# working.net
KiCad netlist of a schematic drawn in EAGLE
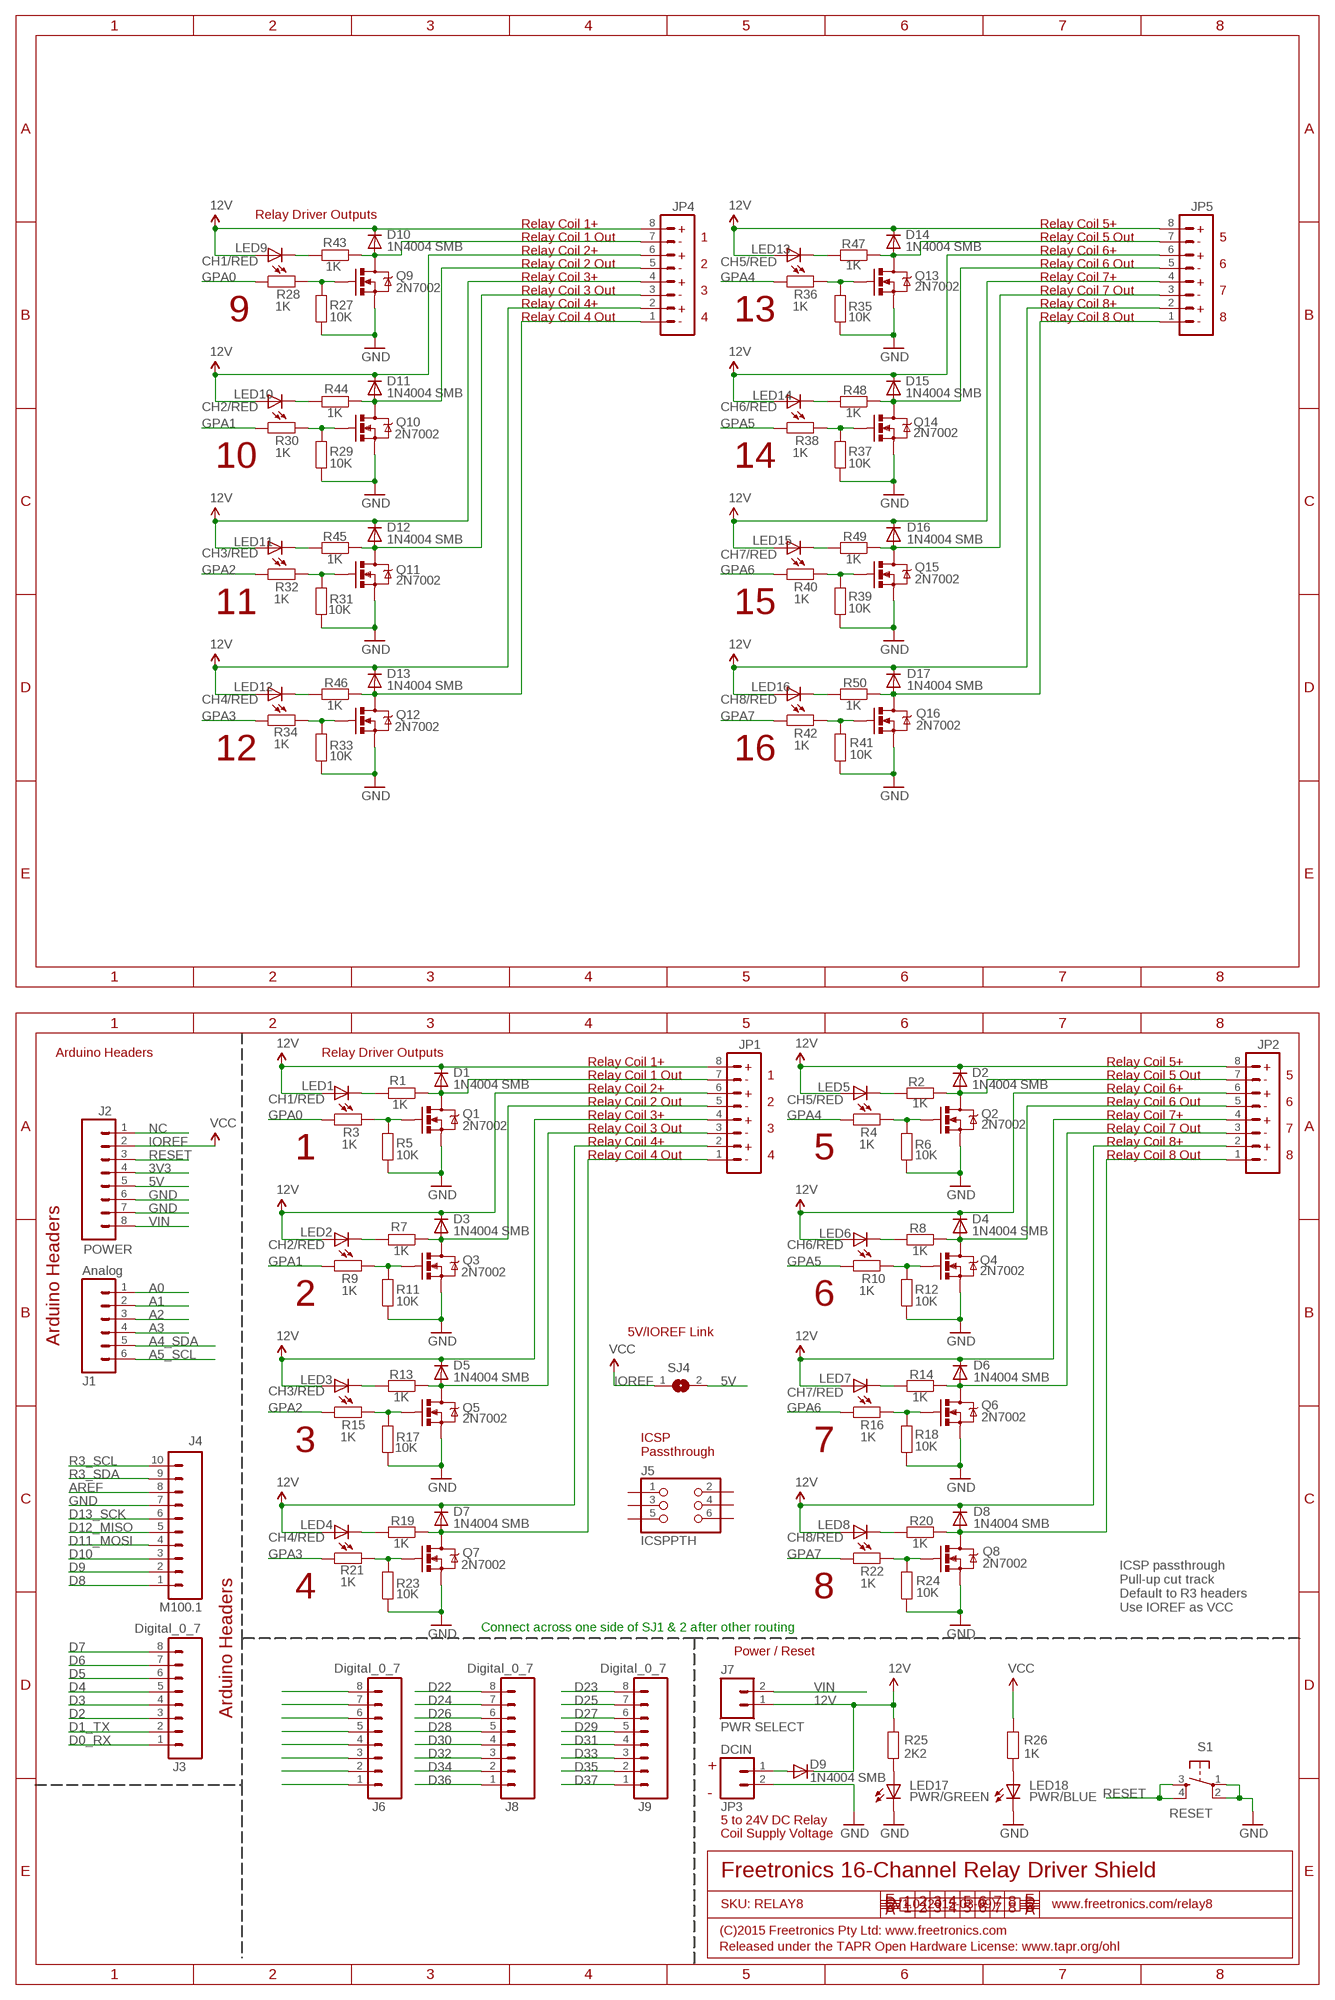
[diagram p0: schematic, sheet 1]

(export (version "E")
  (design (tool "Eeschema 10.0.6"))
  (components
    (comp (ref "D1")
      (value "1N4004 SMB")
      (footprint "eagle-import:SMB-DIODE")
      (libsource (lib "eagle-import") (part "DIODESMB"))
    )
    (comp (ref "D2")
      (value "1N4004 SMB")
      (footprint "eagle-import:SMB-DIODE")
      (libsource (lib "eagle-import") (part "DIODESMB"))
    )
    (comp (ref "D3")
      (value "1N4004 SMB")
      (footprint "eagle-import:SMB-DIODE")
      (libsource (lib "eagle-import") (part "DIODESMB"))
    )
    (comp (ref "D4")
      (value "1N4004 SMB")
      (footprint "eagle-import:SMB-DIODE")
      (libsource (lib "eagle-import") (part "DIODESMB"))
    )
    (comp (ref "D5")
      (value "1N4004 SMB")
      (footprint "eagle-import:SMB-DIODE")
      (libsource (lib "eagle-import") (part "DIODESMB"))
    )
    (comp (ref "D6")
      (value "1N4004 SMB")
      (footprint "eagle-import:SMB-DIODE")
      (libsource (lib "eagle-import") (part "DIODESMB"))
    )
    (comp (ref "D7")
      (value "1N4004 SMB")
      (footprint "eagle-import:SMB-DIODE")
      (libsource (lib "eagle-import") (part "DIODESMB"))
    )
    (comp (ref "D8")
      (value "1N4004 SMB")
      (footprint "eagle-import:SMB-DIODE")
      (libsource (lib "eagle-import") (part "DIODESMB"))
    )
    (comp (ref "D9")
      (value "1N4004 SMB")
      (footprint "eagle-import:SMB-DIODE")
      (libsource (lib "eagle-import") (part "DIODESMB"))
    )
    (comp (ref "D10")
      (value "1N4004 SMB")
      (footprint "eagle-import:SMB-DIODE")
      (libsource (lib "eagle-import") (part "DIODESMB"))
    )
    (comp (ref "D11")
      (value "1N4004 SMB")
      (footprint "eagle-import:SMB-DIODE")
      (libsource (lib "eagle-import") (part "DIODESMB"))
    )
    (comp (ref "D12")
      (value "1N4004 SMB")
      (footprint "eagle-import:SMB-DIODE")
      (libsource (lib "eagle-import") (part "DIODESMB"))
    )
    (comp (ref "D13")
      (value "1N4004 SMB")
      (footprint "eagle-import:SMB-DIODE")
      (libsource (lib "eagle-import") (part "DIODESMB"))
    )
    (comp (ref "D14")
      (value "1N4004 SMB")
      (footprint "eagle-import:SMB-DIODE")
      (libsource (lib "eagle-import") (part "DIODESMB"))
    )
    (comp (ref "D15")
      (value "1N4004 SMB")
      (footprint "eagle-import:SMB-DIODE")
      (libsource (lib "eagle-import") (part "DIODESMB"))
    )
    (comp (ref "D16")
      (value "1N4004 SMB")
      (footprint "eagle-import:SMB-DIODE")
      (libsource (lib "eagle-import") (part "DIODESMB"))
    )
    (comp (ref "D17")
      (value "1N4004 SMB")
      (footprint "eagle-import:SMB-DIODE")
      (libsource (lib "eagle-import") (part "DIODESMB"))
    )
    (comp (ref "J1")
      (value "Analog")
      (footprint "eagle-import:1X06")
      (libsource (lib "eagle-import") (part "M06SIP"))
    )
    (comp (ref "J2")
      (value "POWER")
      (footprint "eagle-import:1X08")
      (libsource (lib "eagle-import") (part "M08"))
    )
    (comp (ref "J3")
      (value "Digital_0_7")
      (footprint "eagle-import:1X08")
      (libsource (lib "eagle-import") (part "M08"))
    )
    (comp (ref "J4")
      (value "M100.1")
      (footprint "eagle-import:1X10")
      (libsource (lib "eagle-import") (part "M100.1"))
    )
    (comp (ref "J5")
      (value "ICSPPTH")
      (footprint "eagle-import:2X03PTH")
      (libsource (lib "eagle-import") (part "ICSPPTH"))
    )
    (comp (ref "J6")
      (value "Digital_0_7")
      (footprint "eagle-import:1X08")
      (libsource (lib "eagle-import") (part "M08"))
    )
    (comp (ref "J7")
      (value "PWR SELECT")
      (footprint "eagle-import:1X02")
      (libsource (lib "eagle-import") (part "M02PTH"))
    )
    (comp (ref "J8")
      (value "Digital_0_7")
      (footprint "eagle-import:1X08")
      (libsource (lib "eagle-import") (part "M08"))
    )
    (comp (ref "J9")
      (value "Digital_0_7")
      (footprint "eagle-import:1X08")
      (libsource (lib "eagle-import") (part "M08"))
    )
    (comp (ref "JP1")
      (value "M08")
      (footprint "eagle-import:TERMINALBLOCK_3.5MM_8")
      (libsource (lib "eagle-import") (part "freetronics-master-v1_M08"))
    )
    (comp (ref "JP2")
      (value "M08")
      (footprint "eagle-import:TERMINALBLOCK_3.5MM_8")
      (libsource (lib "eagle-import") (part "freetronics-master-v1_M08"))
    )
    (comp (ref "JP3")
      (value "DCIN")
      (footprint "eagle-import:SCREWTERMINAL-3.5MM-2")
      (libsource (lib "eagle-import") (part "freetronics-master-v1.1_M023.5MM"))
    )
    (comp (ref "JP4")
      (value "M08")
      (footprint "eagle-import:TERMINALBLOCK_3.5MM_8")
      (libsource (lib "eagle-import") (part "freetronics-master-v1_M08"))
    )
    (comp (ref "JP5")
      (value "M08")
      (footprint "eagle-import:TERMINALBLOCK_3.5MM_8")
      (libsource (lib "eagle-import") (part "freetronics-master-v1_M08"))
    )
    (comp (ref "LED1")
      (value "CH1/RED")
      (footprint "eagle-import:LED-0603")
      (libsource (lib "eagle-import") (part "LED0603"))
    )
    (comp (ref "LED2")
      (value "CH2/RED")
      (footprint "eagle-import:LED-0603")
      (libsource (lib "eagle-import") (part "LED0603"))
    )
    (comp (ref "LED3")
      (value "CH3/RED")
      (footprint "eagle-import:LED-0603")
      (libsource (lib "eagle-import") (part "LED0603"))
    )
    (comp (ref "LED4")
      (value "CH4/RED")
      (footprint "eagle-import:LED-0603")
      (libsource (lib "eagle-import") (part "LED0603"))
    )
    (comp (ref "LED5")
      (value "CH5/RED")
      (footprint "eagle-import:LED-0603")
      (libsource (lib "eagle-import") (part "LED0603"))
    )
    (comp (ref "LED6")
      (value "CH6/RED")
      (footprint "eagle-import:LED-0603")
      (libsource (lib "eagle-import") (part "LED0603"))
    )
    (comp (ref "LED7")
      (value "CH7/RED")
      (footprint "eagle-import:LED-0603")
      (libsource (lib "eagle-import") (part "LED0603"))
    )
    (comp (ref "LED8")
      (value "CH8/RED")
      (footprint "eagle-import:LED-0603")
      (libsource (lib "eagle-import") (part "LED0603"))
    )
    (comp (ref "LED9")
      (value "CH1/RED")
      (footprint "eagle-import:LED-0603")
      (libsource (lib "eagle-import") (part "LED0603"))
    )
    (comp (ref "LED10")
      (value "CH2/RED")
      (footprint "eagle-import:LED-0603")
      (libsource (lib "eagle-import") (part "LED0603"))
    )
    (comp (ref "LED11")
      (value "CH3/RED")
      (footprint "eagle-import:LED-0603")
      (libsource (lib "eagle-import") (part "LED0603"))
    )
    (comp (ref "LED12")
      (value "CH4/RED")
      (footprint "eagle-import:LED-0603")
      (libsource (lib "eagle-import") (part "LED0603"))
    )
    (comp (ref "LED13")
      (value "CH5/RED")
      (footprint "eagle-import:LED-0603")
      (libsource (lib "eagle-import") (part "LED0603"))
    )
    (comp (ref "LED14")
      (value "CH6/RED")
      (footprint "eagle-import:LED-0603")
      (libsource (lib "eagle-import") (part "LED0603"))
    )
    (comp (ref "LED15")
      (value "CH7/RED")
      (footprint "eagle-import:LED-0603")
      (libsource (lib "eagle-import") (part "LED0603"))
    )
    (comp (ref "LED16")
      (value "CH8/RED")
      (footprint "eagle-import:LED-0603")
      (libsource (lib "eagle-import") (part "LED0603"))
    )
    (comp (ref "LED17")
      (value "PWR/GREEN")
      (footprint "eagle-import:LED-0603")
      (libsource (lib "eagle-import") (part "LED0603"))
    )
    (comp (ref "LED18")
      (value "PWR/BLUE")
      (footprint "eagle-import:LED-0603")
      (libsource (lib "eagle-import") (part "LED0603"))
    )
    (comp (ref "Q1")
      (value "2N7002")
      (footprint "eagle-import:SOT23-3")
      (libsource (lib "eagle-import") (part "MOSFET-NCHANNELSMD"))
    )
    (comp (ref "Q2")
      (value "2N7002")
      (footprint "eagle-import:SOT23-3")
      (libsource (lib "eagle-import") (part "MOSFET-NCHANNELSMD"))
    )
    (comp (ref "Q3")
      (value "2N7002")
      (footprint "eagle-import:SOT23-3")
      (libsource (lib "eagle-import") (part "MOSFET-NCHANNELSMD"))
    )
    (comp (ref "Q4")
      (value "2N7002")
      (footprint "eagle-import:SOT23-3")
      (libsource (lib "eagle-import") (part "MOSFET-NCHANNELSMD"))
    )
    (comp (ref "Q5")
      (value "2N7002")
      (footprint "eagle-import:SOT23-3")
      (libsource (lib "eagle-import") (part "MOSFET-NCHANNELSMD"))
    )
    (comp (ref "Q6")
      (value "2N7002")
      (footprint "eagle-import:SOT23-3")
      (libsource (lib "eagle-import") (part "MOSFET-NCHANNELSMD"))
    )
    (comp (ref "Q7")
      (value "2N7002")
      (footprint "eagle-import:SOT23-3")
      (libsource (lib "eagle-import") (part "MOSFET-NCHANNELSMD"))
    )
    (comp (ref "Q8")
      (value "2N7002")
      (footprint "eagle-import:SOT23-3")
      (libsource (lib "eagle-import") (part "MOSFET-NCHANNELSMD"))
    )
    (comp (ref "Q9")
      (value "2N7002")
      (footprint "eagle-import:SOT23-3")
      (libsource (lib "eagle-import") (part "MOSFET-NCHANNELSMD"))
    )
    (comp (ref "Q10")
      (value "2N7002")
      (footprint "eagle-import:SOT23-3")
      (libsource (lib "eagle-import") (part "MOSFET-NCHANNELSMD"))
    )
    (comp (ref "Q11")
      (value "2N7002")
      (footprint "eagle-import:SOT23-3")
      (libsource (lib "eagle-import") (part "MOSFET-NCHANNELSMD"))
    )
    (comp (ref "Q12")
      (value "2N7002")
      (footprint "eagle-import:SOT23-3")
      (libsource (lib "eagle-import") (part "MOSFET-NCHANNELSMD"))
    )
    (comp (ref "Q13")
      (value "2N7002")
      (footprint "eagle-import:SOT23-3")
      (libsource (lib "eagle-import") (part "MOSFET-NCHANNELSMD"))
    )
    (comp (ref "Q14")
      (value "2N7002")
      (footprint "eagle-import:SOT23-3")
      (libsource (lib "eagle-import") (part "MOSFET-NCHANNELSMD"))
    )
    (comp (ref "Q15")
      (value "2N7002")
      (footprint "eagle-import:SOT23-3")
      (libsource (lib "eagle-import") (part "MOSFET-NCHANNELSMD"))
    )
    (comp (ref "Q16")
      (value "2N7002")
      (footprint "eagle-import:SOT23-3")
      (libsource (lib "eagle-import") (part "MOSFET-NCHANNELSMD"))
    )
    (comp (ref "R1")
      (value "1K")
      (footprint "eagle-import:0603")
      (libsource (lib "eagle-import") (part "RESISTOR0603"))
    )
    (comp (ref "R2")
      (value "1K")
      (footprint "eagle-import:0603")
      (libsource (lib "eagle-import") (part "RESISTOR0603"))
    )
    (comp (ref "R3")
      (value "1K")
      (footprint "eagle-import:0603")
      (libsource (lib "eagle-import") (part "RESISTOR0603"))
    )
    (comp (ref "R4")
      (value "1K")
      (footprint "eagle-import:0603")
      (libsource (lib "eagle-import") (part "RESISTOR0603"))
    )
    (comp (ref "R5")
      (value "10K")
      (footprint "eagle-import:0603")
      (libsource (lib "eagle-import") (part "RESISTOR0603"))
    )
    (comp (ref "R6")
      (value "10K")
      (footprint "eagle-import:0603")
      (libsource (lib "eagle-import") (part "RESISTOR0603"))
    )
    (comp (ref "R7")
      (value "1K")
      (footprint "eagle-import:0603")
      (libsource (lib "eagle-import") (part "RESISTOR0603"))
    )
    (comp (ref "R8")
      (value "1K")
      (footprint "eagle-import:0603")
      (libsource (lib "eagle-import") (part "RESISTOR0603"))
    )
    (comp (ref "R9")
      (value "1K")
      (footprint "eagle-import:0603")
      (libsource (lib "eagle-import") (part "RESISTOR0603"))
    )
    (comp (ref "R10")
      (value "1K")
      (footprint "eagle-import:0603")
      (libsource (lib "eagle-import") (part "RESISTOR0603"))
    )
    (comp (ref "R11")
      (value "10K")
      (footprint "eagle-import:0603")
      (libsource (lib "eagle-import") (part "RESISTOR0603"))
    )
    (comp (ref "R12")
      (value "10K")
      (footprint "eagle-import:0603")
      (libsource (lib "eagle-import") (part "RESISTOR0603"))
    )
    (comp (ref "R13")
      (value "1K")
      (footprint "eagle-import:0603")
      (libsource (lib "eagle-import") (part "RESISTOR0603"))
    )
    (comp (ref "R14")
      (value "1K")
      (footprint "eagle-import:0603")
      (libsource (lib "eagle-import") (part "RESISTOR0603"))
    )
    (comp (ref "R15")
      (value "1K")
      (footprint "eagle-import:0603")
      (libsource (lib "eagle-import") (part "RESISTOR0603"))
    )
    (comp (ref "R16")
      (value "1K")
      (footprint "eagle-import:0603")
      (libsource (lib "eagle-import") (part "RESISTOR0603"))
    )
    (comp (ref "R17")
      (value "10K")
      (footprint "eagle-import:0603")
      (libsource (lib "eagle-import") (part "RESISTOR0603"))
    )
    (comp (ref "R18")
      (value "10K")
      (footprint "eagle-import:0603")
      (libsource (lib "eagle-import") (part "RESISTOR0603"))
    )
    (comp (ref "R19")
      (value "1K")
      (footprint "eagle-import:0603")
      (libsource (lib "eagle-import") (part "RESISTOR0603"))
    )
    (comp (ref "R20")
      (value "1K")
      (footprint "eagle-import:0603")
      (libsource (lib "eagle-import") (part "RESISTOR0603"))
    )
    (comp (ref "R21")
      (value "1K")
      (footprint "eagle-import:0603")
      (libsource (lib "eagle-import") (part "RESISTOR0603"))
    )
    (comp (ref "R22")
      (value "1K")
      (footprint "eagle-import:0603")
      (libsource (lib "eagle-import") (part "RESISTOR0603"))
    )
    (comp (ref "R23")
      (value "10K")
      (footprint "eagle-import:0603")
      (libsource (lib "eagle-import") (part "RESISTOR0603"))
    )
    (comp (ref "R24")
      (value "10K")
      (footprint "eagle-import:0603")
      (libsource (lib "eagle-import") (part "RESISTOR0603"))
    )
    (comp (ref "R25")
      (value "2K2")
      (footprint "eagle-import:0603")
      (libsource (lib "eagle-import") (part "RESISTOR0603"))
    )
    (comp (ref "R26")
      (value "1K")
      (footprint "eagle-import:0603")
      (libsource (lib "eagle-import") (part "RESISTOR0603"))
    )
    (comp (ref "R27")
      (value "10K")
      (footprint "eagle-import:0603")
      (libsource (lib "eagle-import") (part "RESISTOR0603"))
    )
    (comp (ref "R28")
      (value "1K")
      (footprint "eagle-import:0603")
      (libsource (lib "eagle-import") (part "RESISTOR0603"))
    )
    (comp (ref "R29")
      (value "10K")
      (footprint "eagle-import:0603")
      (libsource (lib "eagle-import") (part "RESISTOR0603"))
    )
    (comp (ref "R30")
      (value "1K")
      (footprint "eagle-import:0603")
      (libsource (lib "eagle-import") (part "RESISTOR0603"))
    )
    (comp (ref "R31")
      (value "10K")
      (footprint "eagle-import:0603")
      (libsource (lib "eagle-import") (part "RESISTOR0603"))
    )
    (comp (ref "R32")
      (value "1K")
      (footprint "eagle-import:0603")
      (libsource (lib "eagle-import") (part "RESISTOR0603"))
    )
    (comp (ref "R33")
      (value "10K")
      (footprint "eagle-import:0603")
      (libsource (lib "eagle-import") (part "RESISTOR0603"))
    )
    (comp (ref "R34")
      (value "1K")
      (footprint "eagle-import:0603")
      (libsource (lib "eagle-import") (part "RESISTOR0603"))
    )
    (comp (ref "R35")
      (value "10K")
      (footprint "eagle-import:0603")
      (libsource (lib "eagle-import") (part "RESISTOR0603"))
    )
    (comp (ref "R36")
      (value "1K")
      (footprint "eagle-import:0603")
      (libsource (lib "eagle-import") (part "RESISTOR0603"))
    )
    (comp (ref "R37")
      (value "10K")
      (footprint "eagle-import:0603")
      (libsource (lib "eagle-import") (part "RESISTOR0603"))
    )
    (comp (ref "R38")
      (value "1K")
      (footprint "eagle-import:0603")
      (libsource (lib "eagle-import") (part "RESISTOR0603"))
    )
    (comp (ref "R39")
      (value "10K")
      (footprint "eagle-import:0603")
      (libsource (lib "eagle-import") (part "RESISTOR0603"))
    )
    (comp (ref "R40")
      (value "1K")
      (footprint "eagle-import:0603")
      (libsource (lib "eagle-import") (part "RESISTOR0603"))
    )
    (comp (ref "R41")
      (value "10K")
      (footprint "eagle-import:0603")
      (libsource (lib "eagle-import") (part "RESISTOR0603"))
    )
    (comp (ref "R42")
      (value "1K")
      (footprint "eagle-import:0603")
      (libsource (lib "eagle-import") (part "RESISTOR0603"))
    )
    (comp (ref "R43")
      (value "1K")
      (footprint "eagle-import:0603")
      (libsource (lib "eagle-import") (part "RESISTOR0603"))
    )
    (comp (ref "R44")
      (value "1K")
      (footprint "eagle-import:0603")
      (libsource (lib "eagle-import") (part "RESISTOR0603"))
    )
    (comp (ref "R45")
      (value "1K")
      (footprint "eagle-import:0603")
      (libsource (lib "eagle-import") (part "RESISTOR0603"))
    )
    (comp (ref "R46")
      (value "1K")
      (footprint "eagle-import:0603")
      (libsource (lib "eagle-import") (part "RESISTOR0603"))
    )
    (comp (ref "R47")
      (value "1K")
      (footprint "eagle-import:0603")
      (libsource (lib "eagle-import") (part "RESISTOR0603"))
    )
    (comp (ref "R48")
      (value "1K")
      (footprint "eagle-import:0603")
      (libsource (lib "eagle-import") (part "RESISTOR0603"))
    )
    (comp (ref "R49")
      (value "1K")
      (footprint "eagle-import:0603")
      (libsource (lib "eagle-import") (part "RESISTOR0603"))
    )
    (comp (ref "R50")
      (value "1K")
      (footprint "eagle-import:0603")
      (libsource (lib "eagle-import") (part "RESISTOR0603"))
    )
    (comp (ref "S1")
      (value "RESET")
      (footprint "eagle-import:TACTILE_SWITCH_SMD")
      (libsource (lib "eagle-import") (part "TAC_SWITCHSMD"))
    )
    (comp (ref "SJ4")
      (value "SJN")
      (footprint "eagle-import:SJ")
      (libsource (lib "eagle-import") (part "SJN"))
    )
  )
  (nets
    (net (code "1") (name "/3V3") (class "Default")
      (node (ref "J2") (pin "4") (pinfunction "4_4") (pintype "passive"))
    )
    (net (code "2") (name "/5V") (class "Default")
      (node (ref "J2") (pin "5") (pinfunction "5_5") (pintype "passive"))
      (node (ref "SJ4") (pin "2") (pinfunction "2_2") (pintype "passive"))
    )
    (net (code "3") (name "/A0") (class "Default")
      (node (ref "J1") (pin "1") (pinfunction "1_1") (pintype "passive"))
    )
    (net (code "4") (name "/A1") (class "Default")
      (node (ref "J1") (pin "2") (pinfunction "2_2") (pintype "passive"))
    )
    (net (code "5") (name "/A2") (class "Default")
      (node (ref "J1") (pin "3") (pinfunction "3_3") (pintype "passive"))
    )
    (net (code "6") (name "/A3") (class "Default")
      (node (ref "J1") (pin "4") (pinfunction "4_4") (pintype "passive"))
    )
    (net (code "7") (name "/A4_SDA") (class "Default")
      (node (ref "J1") (pin "5") (pinfunction "5_5") (pintype "passive"))
    )
    (net (code "8") (name "/A5_SCL") (class "Default")
      (node (ref "J1") (pin "6") (pinfunction "6_6") (pintype "passive"))
    )
    (net (code "9") (name "/AREF") (class "Default")
      (node (ref "J4") (pin "8") (pinfunction "8_8") (pintype "passive"))
    )
    (net (code "10") (name "/D0_RX") (class "Default")
      (node (ref "J3") (pin "1") (pinfunction "1_1") (pintype "passive"))
    )
    (net (code "11") (name "/D1_TX") (class "Default")
      (node (ref "J3") (pin "2") (pinfunction "2_2") (pintype "passive"))
    )
    (net (code "12") (name "/D2") (class "Default")
      (node (ref "J3") (pin "3") (pinfunction "3_3") (pintype "passive"))
    )
    (net (code "13") (name "/D3") (class "Default")
      (node (ref "J3") (pin "4") (pinfunction "4_4") (pintype "passive"))
    )
    (net (code "14") (name "/D4") (class "Default")
      (node (ref "J3") (pin "5") (pinfunction "5_5") (pintype "passive"))
    )
    (net (code "15") (name "/D5") (class "Default")
      (node (ref "J3") (pin "6") (pinfunction "6_6") (pintype "passive"))
    )
    (net (code "16") (name "/D6") (class "Default")
      (node (ref "J3") (pin "7") (pinfunction "7_7") (pintype "passive"))
    )
    (net (code "17") (name "/D7") (class "Default")
      (node (ref "J3") (pin "8") (pinfunction "8_8") (pintype "passive"))
    )
    (net (code "18") (name "/D8") (class "Default")
      (node (ref "J4") (pin "1") (pinfunction "1_1") (pintype "passive"))
    )
    (net (code "19") (name "/D9") (class "Default")
      (node (ref "J4") (pin "2") (pinfunction "2_2") (pintype "passive"))
    )
    (net (code "20") (name "/D10") (class "Default")
      (node (ref "J4") (pin "3") (pinfunction "3_3") (pintype "passive"))
    )
    (net (code "21") (name "/D11_MOSI") (class "Default")
      (node (ref "J4") (pin "4") (pinfunction "4_4") (pintype "passive"))
    )
    (net (code "22") (name "/D12_MISO") (class "Default")
      (node (ref "J4") (pin "5") (pinfunction "5_5") (pintype "passive"))
    )
    (net (code "23") (name "/D13_SCK") (class "Default")
      (node (ref "J4") (pin "6") (pinfunction "6_6") (pintype "passive"))
    )
    (net (code "24") (name "/D22") (class "Default")
      (node (ref "J8") (pin "8") (pinfunction "8_8") (pintype "passive"))
    )
    (net (code "25") (name "/D23") (class "Default")
      (node (ref "J9") (pin "8") (pinfunction "8_8") (pintype "passive"))
    )
    (net (code "26") (name "/D24") (class "Default")
      (node (ref "J8") (pin "7") (pinfunction "7_7") (pintype "passive"))
    )
    (net (code "27") (name "/D25") (class "Default")
      (node (ref "J9") (pin "7") (pinfunction "7_7") (pintype "passive"))
    )
    (net (code "28") (name "/D26") (class "Default")
      (node (ref "J8") (pin "6") (pinfunction "6_6") (pintype "passive"))
    )
    (net (code "29") (name "/D27") (class "Default")
      (node (ref "J9") (pin "6") (pinfunction "6_6") (pintype "passive"))
    )
    (net (code "30") (name "/D28") (class "Default")
      (node (ref "J8") (pin "5") (pinfunction "5_5") (pintype "passive"))
    )
    (net (code "31") (name "/D29") (class "Default")
      (node (ref "J9") (pin "5") (pinfunction "5_5") (pintype "passive"))
    )
    (net (code "32") (name "/D30") (class "Default")
      (node (ref "J8") (pin "4") (pinfunction "4_4") (pintype "passive"))
    )
    (net (code "33") (name "/D31") (class "Default")
      (node (ref "J9") (pin "4") (pinfunction "4_4") (pintype "passive"))
    )
    (net (code "34") (name "/D32") (class "Default")
      (node (ref "J8") (pin "3") (pinfunction "3_3") (pintype "passive"))
    )
    (net (code "35") (name "/D33") (class "Default")
      (node (ref "J9") (pin "3") (pinfunction "3_3") (pintype "passive"))
    )
    (net (code "36") (name "/D34") (class "Default")
      (node (ref "J8") (pin "2") (pinfunction "2_2") (pintype "passive"))
    )
    (net (code "37") (name "/D35") (class "Default")
      (node (ref "J9") (pin "2") (pinfunction "2_2") (pintype "passive"))
    )
    (net (code "38") (name "/D36") (class "Default")
      (node (ref "J8") (pin "1") (pinfunction "1_1") (pintype "passive"))
    )
    (net (code "39") (name "/D37") (class "Default")
      (node (ref "J9") (pin "1") (pinfunction "1_1") (pintype "passive"))
    )
    (net (code "40") (name "/GPA0") (class "Default")
      (node (ref "R28") (pin "2") (pinfunction "2_2") (pintype "passive"))
      (node (ref "R3") (pin "2") (pinfunction "2_2") (pintype "passive"))
    )
    (net (code "41") (name "/GPA1") (class "Default")
      (node (ref "R30") (pin "2") (pinfunction "2_2") (pintype "passive"))
      (node (ref "R9") (pin "2") (pinfunction "2_2") (pintype "passive"))
    )
    (net (code "42") (name "/GPA2") (class "Default")
      (node (ref "R15") (pin "2") (pinfunction "2_2") (pintype "passive"))
      (node (ref "R32") (pin "2") (pinfunction "2_2") (pintype "passive"))
    )
    (net (code "43") (name "/GPA3") (class "Default")
      (node (ref "R21") (pin "2") (pinfunction "2_2") (pintype "passive"))
      (node (ref "R34") (pin "2") (pinfunction "2_2") (pintype "passive"))
    )
    (net (code "44") (name "/GPA4") (class "Default")
      (node (ref "R36") (pin "2") (pinfunction "2_2") (pintype "passive"))
      (node (ref "R4") (pin "2") (pinfunction "2_2") (pintype "passive"))
    )
    (net (code "45") (name "/GPA5") (class "Default")
      (node (ref "R10") (pin "2") (pinfunction "2_2") (pintype "passive"))
      (node (ref "R38") (pin "2") (pinfunction "2_2") (pintype "passive"))
    )
    (net (code "46") (name "/GPA6") (class "Default")
      (node (ref "R16") (pin "2") (pinfunction "2_2") (pintype "passive"))
      (node (ref "R40") (pin "2") (pinfunction "2_2") (pintype "passive"))
    )
    (net (code "47") (name "/GPA7") (class "Default")
      (node (ref "R22") (pin "2") (pinfunction "2_2") (pintype "passive"))
      (node (ref "R42") (pin "2") (pinfunction "2_2") (pintype "passive"))
    )
    (net (code "48") (name "/NC") (class "Default")
      (node (ref "J2") (pin "1") (pinfunction "1_1") (pintype "passive"))
    )
    (net (code "49") (name "/R3_SCL") (class "Default")
      (node (ref "J4") (pin "10") (pinfunction "10_10") (pintype "passive"))
    )
    (net (code "50") (name "/R3_SDA") (class "Default")
      (node (ref "J4") (pin "9") (pinfunction "9_9") (pintype "passive"))
    )
    (net (code "51") (name "/RESET") (class "Default")
      (node (ref "J2") (pin "3") (pinfunction "3_3") (pintype "passive"))
      (node (ref "S1") (pin "3") (pinfunction "3_3") (pintype "passive"))
      (node (ref "S1") (pin "4") (pinfunction "4_4") (pintype "passive"))
    )
    (net (code "52") (name "/VIN") (class "Default")
      (node (ref "J2") (pin "8") (pinfunction "8_8") (pintype "passive"))
      (node (ref "J7") (pin "2") (pinfunction "2_2") (pintype "passive"))
    )
    (net (code "53") (name "12V") (class "Default")
      (node (ref "D1") (pin "C") (pinfunction "C_C") (pintype "passive"))
      (node (ref "D10") (pin "C") (pinfunction "C_C") (pintype "passive"))
      (node (ref "D11") (pin "C") (pinfunction "C_C") (pintype "passive"))
      (node (ref "D12") (pin "C") (pinfunction "C_C") (pintype "passive"))
      (node (ref "D13") (pin "C") (pinfunction "C_C") (pintype "passive"))
      (node (ref "D14") (pin "C") (pinfunction "C_C") (pintype "passive"))
      (node (ref "D15") (pin "C") (pinfunction "C_C") (pintype "passive"))
      (node (ref "D16") (pin "C") (pinfunction "C_C") (pintype "passive"))
      (node (ref "D17") (pin "C") (pinfunction "C_C") (pintype "passive"))
      (node (ref "D2") (pin "C") (pinfunction "C_C") (pintype "passive"))
      (node (ref "D3") (pin "C") (pinfunction "C_C") (pintype "passive"))
      (node (ref "D4") (pin "C") (pinfunction "C_C") (pintype "passive"))
      (node (ref "D5") (pin "C") (pinfunction "C_C") (pintype "passive"))
      (node (ref "D6") (pin "C") (pinfunction "C_C") (pintype "passive"))
      (node (ref "D7") (pin "C") (pinfunction "C_C") (pintype "passive"))
      (node (ref "D8") (pin "C") (pinfunction "C_C") (pintype "passive"))
      (node (ref "D9") (pin "C") (pinfunction "C_C") (pintype "passive"))
      (node (ref "J7") (pin "1") (pinfunction "1_1") (pintype "passive"))
      (node (ref "JP1") (pin "2") (pinfunction "2_2") (pintype "passive"))
      (node (ref "JP1") (pin "4") (pinfunction "4_4") (pintype "passive"))
      (node (ref "JP1") (pin "6") (pinfunction "6_6") (pintype "passive"))
      (node (ref "JP1") (pin "8") (pinfunction "8_8") (pintype "passive"))
      (node (ref "JP2") (pin "2") (pinfunction "2_2") (pintype "passive"))
      (node (ref "JP2") (pin "4") (pinfunction "4_4") (pintype "passive"))
      (node (ref "JP2") (pin "6") (pinfunction "6_6") (pintype "passive"))
      (node (ref "JP2") (pin "8") (pinfunction "8_8") (pintype "passive"))
      (node (ref "JP4") (pin "2") (pinfunction "2_2") (pintype "passive"))
      (node (ref "JP4") (pin "4") (pinfunction "4_4") (pintype "passive"))
      (node (ref "JP4") (pin "6") (pinfunction "6_6") (pintype "passive"))
      (node (ref "JP4") (pin "8") (pinfunction "8_8") (pintype "passive"))
      (node (ref "JP5") (pin "2") (pinfunction "2_2") (pintype "passive"))
      (node (ref "JP5") (pin "4") (pinfunction "4_4") (pintype "passive"))
      (node (ref "JP5") (pin "6") (pinfunction "6_6") (pintype "passive"))
      (node (ref "JP5") (pin "8") (pinfunction "8_8") (pintype "passive"))
      (node (ref "LED1") (pin "A") (pinfunction "A_A") (pintype "passive"))
      (node (ref "LED10") (pin "A") (pinfunction "A_A") (pintype "passive"))
      (node (ref "LED11") (pin "A") (pinfunction "A_A") (pintype "passive"))
      (node (ref "LED12") (pin "A") (pinfunction "A_A") (pintype "passive"))
      (node (ref "LED13") (pin "A") (pinfunction "A_A") (pintype "passive"))
      (node (ref "LED14") (pin "A") (pinfunction "A_A") (pintype "passive"))
      (node (ref "LED15") (pin "A") (pinfunction "A_A") (pintype "passive"))
      (node (ref "LED16") (pin "A") (pinfunction "A_A") (pintype "passive"))
      (node (ref "LED2") (pin "A") (pinfunction "A_A") (pintype "passive"))
      (node (ref "LED3") (pin "A") (pinfunction "A_A") (pintype "passive"))
      (node (ref "LED4") (pin "A") (pinfunction "A_A") (pintype "passive"))
      (node (ref "LED5") (pin "A") (pinfunction "A_A") (pintype "passive"))
      (node (ref "LED6") (pin "A") (pinfunction "A_A") (pintype "passive"))
      (node (ref "LED7") (pin "A") (pinfunction "A_A") (pintype "passive"))
      (node (ref "LED8") (pin "A") (pinfunction "A_A") (pintype "passive"))
      (node (ref "LED9") (pin "A") (pinfunction "A_A") (pintype "passive"))
      (node (ref "R25") (pin "2") (pinfunction "2_2") (pintype "passive"))
    )
    (net (code "54") (name "GND") (class "Default")
      (node (ref "J2") (pin "6") (pinfunction "6_6") (pintype "passive"))
      (node (ref "J2") (pin "7") (pinfunction "7_7") (pintype "passive"))
      (node (ref "J4") (pin "7") (pinfunction "7_7") (pintype "passive"))
      (node (ref "JP3") (pin "2") (pinfunction "2_2") (pintype "passive"))
      (node (ref "LED17") (pin "C") (pinfunction "C_C") (pintype "passive"))
      (node (ref "LED18") (pin "C") (pinfunction "C_C") (pintype "passive"))
      (node (ref "Q1") (pin "2") (pinfunction "S_2") (pintype "passive"))
      (node (ref "Q10") (pin "2") (pinfunction "S_2") (pintype "passive"))
      (node (ref "Q11") (pin "2") (pinfunction "S_2") (pintype "passive"))
      (node (ref "Q12") (pin "2") (pinfunction "S_2") (pintype "passive"))
      (node (ref "Q13") (pin "2") (pinfunction "S_2") (pintype "passive"))
      (node (ref "Q14") (pin "2") (pinfunction "S_2") (pintype "passive"))
      (node (ref "Q15") (pin "2") (pinfunction "S_2") (pintype "passive"))
      (node (ref "Q16") (pin "2") (pinfunction "S_2") (pintype "passive"))
      (node (ref "Q2") (pin "2") (pinfunction "S_2") (pintype "passive"))
      (node (ref "Q3") (pin "2") (pinfunction "S_2") (pintype "passive"))
      (node (ref "Q4") (pin "2") (pinfunction "S_2") (pintype "passive"))
      (node (ref "Q5") (pin "2") (pinfunction "S_2") (pintype "passive"))
      (node (ref "Q6") (pin "2") (pinfunction "S_2") (pintype "passive"))
      (node (ref "Q7") (pin "2") (pinfunction "S_2") (pintype "passive"))
      (node (ref "Q8") (pin "2") (pinfunction "S_2") (pintype "passive"))
      (node (ref "Q9") (pin "2") (pinfunction "S_2") (pintype "passive"))
      (node (ref "R11") (pin "1") (pinfunction "1_1") (pintype "passive"))
      (node (ref "R12") (pin "1") (pinfunction "1_1") (pintype "passive"))
      (node (ref "R17") (pin "1") (pinfunction "1_1") (pintype "passive"))
      (node (ref "R18") (pin "1") (pinfunction "1_1") (pintype "passive"))
      (node (ref "R23") (pin "1") (pinfunction "1_1") (pintype "passive"))
      (node (ref "R24") (pin "1") (pinfunction "1_1") (pintype "passive"))
      (node (ref "R27") (pin "1") (pinfunction "1_1") (pintype "passive"))
      (node (ref "R29") (pin "1") (pinfunction "1_1") (pintype "passive"))
      (node (ref "R31") (pin "1") (pinfunction "1_1") (pintype "passive"))
      (node (ref "R33") (pin "1") (pinfunction "1_1") (pintype "passive"))
      (node (ref "R35") (pin "1") (pinfunction "1_1") (pintype "passive"))
      (node (ref "R37") (pin "1") (pinfunction "1_1") (pintype "passive"))
      (node (ref "R39") (pin "1") (pinfunction "1_1") (pintype "passive"))
      (node (ref "R41") (pin "1") (pinfunction "1_1") (pintype "passive"))
      (node (ref "R5") (pin "1") (pinfunction "1_1") (pintype "passive"))
      (node (ref "R6") (pin "1") (pinfunction "1_1") (pintype "passive"))
      (node (ref "S1") (pin "1") (pinfunction "1_1") (pintype "passive"))
      (node (ref "S1") (pin "2") (pinfunction "2_2") (pintype "passive"))
    )
    (net (code "55") (name "Net-(D9-PadA)") (class "Default")
      (node (ref "D9") (pin "A") (pinfunction "A_A") (pintype "passive"))
      (node (ref "JP3") (pin "1") (pinfunction "1_1") (pintype "passive"))
    )
    (net (code "56") (name "Net-(LED1-PadC)") (class "Default")
      (node (ref "LED1") (pin "C") (pinfunction "C_C") (pintype "passive"))
      (node (ref "R1") (pin "1") (pinfunction "1_1") (pintype "passive"))
    )
    (net (code "57") (name "Net-(LED2-PadC)") (class "Default")
      (node (ref "LED2") (pin "C") (pinfunction "C_C") (pintype "passive"))
      (node (ref "R7") (pin "1") (pinfunction "1_1") (pintype "passive"))
    )
    (net (code "58") (name "Net-(LED3-PadC)") (class "Default")
      (node (ref "LED3") (pin "C") (pinfunction "C_C") (pintype "passive"))
      (node (ref "R13") (pin "1") (pinfunction "1_1") (pintype "passive"))
    )
    (net (code "59") (name "Net-(LED4-PadC)") (class "Default")
      (node (ref "LED4") (pin "C") (pinfunction "C_C") (pintype "passive"))
      (node (ref "R19") (pin "1") (pinfunction "1_1") (pintype "passive"))
    )
    (net (code "60") (name "Net-(LED5-PadC)") (class "Default")
      (node (ref "LED5") (pin "C") (pinfunction "C_C") (pintype "passive"))
      (node (ref "R2") (pin "1") (pinfunction "1_1") (pintype "passive"))
    )
    (net (code "61") (name "Net-(LED6-PadC)") (class "Default")
      (node (ref "LED6") (pin "C") (pinfunction "C_C") (pintype "passive"))
      (node (ref "R8") (pin "1") (pinfunction "1_1") (pintype "passive"))
    )
    (net (code "62") (name "Net-(LED7-PadC)") (class "Default")
      (node (ref "LED7") (pin "C") (pinfunction "C_C") (pintype "passive"))
      (node (ref "R14") (pin "1") (pinfunction "1_1") (pintype "passive"))
    )
    (net (code "63") (name "Net-(LED8-PadC)") (class "Default")
      (node (ref "LED8") (pin "C") (pinfunction "C_C") (pintype "passive"))
      (node (ref "R20") (pin "1") (pinfunction "1_1") (pintype "passive"))
    )
    (net (code "64") (name "Net-(LED9-PadC)") (class "Default")
      (node (ref "LED9") (pin "C") (pinfunction "C_C") (pintype "passive"))
      (node (ref "R43") (pin "1") (pinfunction "1_1") (pintype "passive"))
    )
    (net (code "65") (name "Net-(LED10-PadC)") (class "Default")
      (node (ref "LED10") (pin "C") (pinfunction "C_C") (pintype "passive"))
      (node (ref "R44") (pin "1") (pinfunction "1_1") (pintype "passive"))
    )
    (net (code "66") (name "Net-(LED11-PadC)") (class "Default")
      (node (ref "LED11") (pin "C") (pinfunction "C_C") (pintype "passive"))
      (node (ref "R45") (pin "1") (pinfunction "1_1") (pintype "passive"))
    )
    (net (code "67") (name "Net-(LED12-PadC)") (class "Default")
      (node (ref "LED12") (pin "C") (pinfunction "C_C") (pintype "passive"))
      (node (ref "R46") (pin "1") (pinfunction "1_1") (pintype "passive"))
    )
    (net (code "68") (name "Net-(LED13-PadC)") (class "Default")
      (node (ref "LED13") (pin "C") (pinfunction "C_C") (pintype "passive"))
      (node (ref "R47") (pin "1") (pinfunction "1_1") (pintype "passive"))
    )
    (net (code "69") (name "Net-(LED14-PadC)") (class "Default")
      (node (ref "LED14") (pin "C") (pinfunction "C_C") (pintype "passive"))
      (node (ref "R48") (pin "1") (pinfunction "1_1") (pintype "passive"))
    )
    (net (code "70") (name "Net-(LED15-PadC)") (class "Default")
      (node (ref "LED15") (pin "C") (pinfunction "C_C") (pintype "passive"))
      (node (ref "R49") (pin "1") (pinfunction "1_1") (pintype "passive"))
    )
    (net (code "71") (name "Net-(LED16-PadC)") (class "Default")
      (node (ref "LED16") (pin "C") (pinfunction "C_C") (pintype "passive"))
      (node (ref "R50") (pin "1") (pinfunction "1_1") (pintype "passive"))
    )
    (net (code "72") (name "Net-(LED17-PadA)") (class "Default")
      (node (ref "LED17") (pin "A") (pinfunction "A_A") (pintype "passive"))
      (node (ref "R25") (pin "1") (pinfunction "1_1") (pintype "passive"))
    )
    (net (code "73") (name "Net-(LED18-PadA)") (class "Default")
      (node (ref "LED18") (pin "A") (pinfunction "A_A") (pintype "passive"))
      (node (ref "R26") (pin "1") (pinfunction "1_1") (pintype "passive"))
    )
    (net (code "74") (name "Net-(Q1-D)") (class "Default")
      (node (ref "D1") (pin "A") (pinfunction "A_A") (pintype "passive"))
      (node (ref "JP1") (pin "7") (pinfunction "7_7") (pintype "passive"))
      (node (ref "Q1") (pin "3") (pinfunction "D_3") (pintype "passive"))
      (node (ref "R1") (pin "2") (pinfunction "2_2") (pintype "passive"))
    )
    (net (code "75") (name "Net-(Q1-G)") (class "Default")
      (node (ref "Q1") (pin "1") (pinfunction "G_1") (pintype "passive"))
      (node (ref "R3") (pin "1") (pinfunction "1_1") (pintype "passive"))
      (node (ref "R5") (pin "2") (pinfunction "2_2") (pintype "passive"))
    )
    (net (code "76") (name "Net-(Q2-D)") (class "Default")
      (node (ref "D2") (pin "A") (pinfunction "A_A") (pintype "passive"))
      (node (ref "JP2") (pin "7") (pinfunction "7_7") (pintype "passive"))
      (node (ref "Q2") (pin "3") (pinfunction "D_3") (pintype "passive"))
      (node (ref "R2") (pin "2") (pinfunction "2_2") (pintype "passive"))
    )
    (net (code "77") (name "Net-(Q2-G)") (class "Default")
      (node (ref "Q2") (pin "1") (pinfunction "G_1") (pintype "passive"))
      (node (ref "R4") (pin "1") (pinfunction "1_1") (pintype "passive"))
      (node (ref "R6") (pin "2") (pinfunction "2_2") (pintype "passive"))
    )
    (net (code "78") (name "Net-(Q3-D)") (class "Default")
      (node (ref "D3") (pin "A") (pinfunction "A_A") (pintype "passive"))
      (node (ref "JP1") (pin "5") (pinfunction "5_5") (pintype "passive"))
      (node (ref "Q3") (pin "3") (pinfunction "D_3") (pintype "passive"))
      (node (ref "R7") (pin "2") (pinfunction "2_2") (pintype "passive"))
    )
    (net (code "79") (name "Net-(Q3-G)") (class "Default")
      (node (ref "Q3") (pin "1") (pinfunction "G_1") (pintype "passive"))
      (node (ref "R11") (pin "2") (pinfunction "2_2") (pintype "passive"))
      (node (ref "R9") (pin "1") (pinfunction "1_1") (pintype "passive"))
    )
    (net (code "80") (name "Net-(Q4-D)") (class "Default")
      (node (ref "D4") (pin "A") (pinfunction "A_A") (pintype "passive"))
      (node (ref "JP2") (pin "5") (pinfunction "5_5") (pintype "passive"))
      (node (ref "Q4") (pin "3") (pinfunction "D_3") (pintype "passive"))
      (node (ref "R8") (pin "2") (pinfunction "2_2") (pintype "passive"))
    )
    (net (code "81") (name "Net-(Q4-G)") (class "Default")
      (node (ref "Q4") (pin "1") (pinfunction "G_1") (pintype "passive"))
      (node (ref "R10") (pin "1") (pinfunction "1_1") (pintype "passive"))
      (node (ref "R12") (pin "2") (pinfunction "2_2") (pintype "passive"))
    )
    (net (code "82") (name "Net-(Q5-D)") (class "Default")
      (node (ref "D5") (pin "A") (pinfunction "A_A") (pintype "passive"))
      (node (ref "JP1") (pin "3") (pinfunction "3_3") (pintype "passive"))
      (node (ref "Q5") (pin "3") (pinfunction "D_3") (pintype "passive"))
      (node (ref "R13") (pin "2") (pinfunction "2_2") (pintype "passive"))
    )
    (net (code "83") (name "Net-(Q5-G)") (class "Default")
      (node (ref "Q5") (pin "1") (pinfunction "G_1") (pintype "passive"))
      (node (ref "R15") (pin "1") (pinfunction "1_1") (pintype "passive"))
      (node (ref "R17") (pin "2") (pinfunction "2_2") (pintype "passive"))
    )
    (net (code "84") (name "Net-(Q6-D)") (class "Default")
      (node (ref "D6") (pin "A") (pinfunction "A_A") (pintype "passive"))
      (node (ref "JP2") (pin "3") (pinfunction "3_3") (pintype "passive"))
      (node (ref "Q6") (pin "3") (pinfunction "D_3") (pintype "passive"))
      (node (ref "R14") (pin "2") (pinfunction "2_2") (pintype "passive"))
    )
    (net (code "85") (name "Net-(Q6-G)") (class "Default")
      (node (ref "Q6") (pin "1") (pinfunction "G_1") (pintype "passive"))
      (node (ref "R16") (pin "1") (pinfunction "1_1") (pintype "passive"))
      (node (ref "R18") (pin "2") (pinfunction "2_2") (pintype "passive"))
    )
    (net (code "86") (name "Net-(Q7-D)") (class "Default")
      (node (ref "D7") (pin "A") (pinfunction "A_A") (pintype "passive"))
      (node (ref "JP1") (pin "1") (pinfunction "1_1") (pintype "passive"))
      (node (ref "Q7") (pin "3") (pinfunction "D_3") (pintype "passive"))
      (node (ref "R19") (pin "2") (pinfunction "2_2") (pintype "passive"))
    )
    (net (code "87") (name "Net-(Q7-G)") (class "Default")
      (node (ref "Q7") (pin "1") (pinfunction "G_1") (pintype "passive"))
      (node (ref "R21") (pin "1") (pinfunction "1_1") (pintype "passive"))
      (node (ref "R23") (pin "2") (pinfunction "2_2") (pintype "passive"))
    )
    (net (code "88") (name "Net-(Q8-D)") (class "Default")
      (node (ref "D8") (pin "A") (pinfunction "A_A") (pintype "passive"))
      (node (ref "JP2") (pin "1") (pinfunction "1_1") (pintype "passive"))
      (node (ref "Q8") (pin "3") (pinfunction "D_3") (pintype "passive"))
      (node (ref "R20") (pin "2") (pinfunction "2_2") (pintype "passive"))
    )
    (net (code "89") (name "Net-(Q8-G)") (class "Default")
      (node (ref "Q8") (pin "1") (pinfunction "G_1") (pintype "passive"))
      (node (ref "R22") (pin "1") (pinfunction "1_1") (pintype "passive"))
      (node (ref "R24") (pin "2") (pinfunction "2_2") (pintype "passive"))
    )
    (net (code "90") (name "Net-(Q9-D)") (class "Default")
      (node (ref "D10") (pin "A") (pinfunction "A_A") (pintype "passive"))
      (node (ref "JP4") (pin "7") (pinfunction "7_7") (pintype "passive"))
      (node (ref "Q9") (pin "3") (pinfunction "D_3") (pintype "passive"))
      (node (ref "R43") (pin "2") (pinfunction "2_2") (pintype "passive"))
    )
    (net (code "91") (name "Net-(Q9-G)") (class "Default")
      (node (ref "Q9") (pin "1") (pinfunction "G_1") (pintype "passive"))
      (node (ref "R27") (pin "2") (pinfunction "2_2") (pintype "passive"))
      (node (ref "R28") (pin "1") (pinfunction "1_1") (pintype "passive"))
    )
    (net (code "92") (name "Net-(Q10-D)") (class "Default")
      (node (ref "D11") (pin "A") (pinfunction "A_A") (pintype "passive"))
      (node (ref "JP4") (pin "5") (pinfunction "5_5") (pintype "passive"))
      (node (ref "Q10") (pin "3") (pinfunction "D_3") (pintype "passive"))
      (node (ref "R44") (pin "2") (pinfunction "2_2") (pintype "passive"))
    )
    (net (code "93") (name "Net-(Q10-G)") (class "Default")
      (node (ref "Q10") (pin "1") (pinfunction "G_1") (pintype "passive"))
      (node (ref "R29") (pin "2") (pinfunction "2_2") (pintype "passive"))
      (node (ref "R30") (pin "1") (pinfunction "1_1") (pintype "passive"))
    )
    (net (code "94") (name "Net-(Q11-D)") (class "Default")
      (node (ref "D12") (pin "A") (pinfunction "A_A") (pintype "passive"))
      (node (ref "JP4") (pin "3") (pinfunction "3_3") (pintype "passive"))
      (node (ref "Q11") (pin "3") (pinfunction "D_3") (pintype "passive"))
      (node (ref "R45") (pin "2") (pinfunction "2_2") (pintype "passive"))
    )
    (net (code "95") (name "Net-(Q11-G)") (class "Default")
      (node (ref "Q11") (pin "1") (pinfunction "G_1") (pintype "passive"))
      (node (ref "R31") (pin "2") (pinfunction "2_2") (pintype "passive"))
      (node (ref "R32") (pin "1") (pinfunction "1_1") (pintype "passive"))
    )
    (net (code "96") (name "Net-(Q12-D)") (class "Default")
      (node (ref "D13") (pin "A") (pinfunction "A_A") (pintype "passive"))
      (node (ref "JP4") (pin "1") (pinfunction "1_1") (pintype "passive"))
      (node (ref "Q12") (pin "3") (pinfunction "D_3") (pintype "passive"))
      (node (ref "R46") (pin "2") (pinfunction "2_2") (pintype "passive"))
    )
    (net (code "97") (name "Net-(Q12-G)") (class "Default")
      (node (ref "Q12") (pin "1") (pinfunction "G_1") (pintype "passive"))
      (node (ref "R33") (pin "2") (pinfunction "2_2") (pintype "passive"))
      (node (ref "R34") (pin "1") (pinfunction "1_1") (pintype "passive"))
    )
    (net (code "98") (name "Net-(Q13-D)") (class "Default")
      (node (ref "D14") (pin "A") (pinfunction "A_A") (pintype "passive"))
      (node (ref "JP5") (pin "7") (pinfunction "7_7") (pintype "passive"))
      (node (ref "Q13") (pin "3") (pinfunction "D_3") (pintype "passive"))
      (node (ref "R47") (pin "2") (pinfunction "2_2") (pintype "passive"))
    )
    (net (code "99") (name "Net-(Q13-G)") (class "Default")
      (node (ref "Q13") (pin "1") (pinfunction "G_1") (pintype "passive"))
      (node (ref "R35") (pin "2") (pinfunction "2_2") (pintype "passive"))
      (node (ref "R36") (pin "1") (pinfunction "1_1") (pintype "passive"))
    )
    (net (code "100") (name "Net-(Q14-D)") (class "Default")
      (node (ref "D15") (pin "A") (pinfunction "A_A") (pintype "passive"))
      (node (ref "JP5") (pin "5") (pinfunction "5_5") (pintype "passive"))
      (node (ref "Q14") (pin "3") (pinfunction "D_3") (pintype "passive"))
      (node (ref "R48") (pin "2") (pinfunction "2_2") (pintype "passive"))
    )
    (net (code "101") (name "Net-(Q14-G)") (class "Default")
      (node (ref "Q14") (pin "1") (pinfunction "G_1") (pintype "passive"))
      (node (ref "R37") (pin "2") (pinfunction "2_2") (pintype "passive"))
      (node (ref "R38") (pin "1") (pinfunction "1_1") (pintype "passive"))
    )
    (net (code "102") (name "Net-(Q15-D)") (class "Default")
      (node (ref "D16") (pin "A") (pinfunction "A_A") (pintype "passive"))
      (node (ref "JP5") (pin "3") (pinfunction "3_3") (pintype "passive"))
      (node (ref "Q15") (pin "3") (pinfunction "D_3") (pintype "passive"))
      (node (ref "R49") (pin "2") (pinfunction "2_2") (pintype "passive"))
    )
    (net (code "103") (name "Net-(Q15-G)") (class "Default")
      (node (ref "Q15") (pin "1") (pinfunction "G_1") (pintype "passive"))
      (node (ref "R39") (pin "2") (pinfunction "2_2") (pintype "passive"))
      (node (ref "R40") (pin "1") (pinfunction "1_1") (pintype "passive"))
    )
    (net (code "104") (name "Net-(Q16-D)") (class "Default")
      (node (ref "D17") (pin "A") (pinfunction "A_A") (pintype "passive"))
      (node (ref "JP5") (pin "1") (pinfunction "1_1") (pintype "passive"))
      (node (ref "Q16") (pin "3") (pinfunction "D_3") (pintype "passive"))
      (node (ref "R50") (pin "2") (pinfunction "2_2") (pintype "passive"))
    )
    (net (code "105") (name "Net-(Q16-G)") (class "Default")
      (node (ref "Q16") (pin "1") (pinfunction "G_1") (pintype "passive"))
      (node (ref "R41") (pin "2") (pinfunction "2_2") (pintype "passive"))
      (node (ref "R42") (pin "1") (pinfunction "1_1") (pintype "passive"))
    )
    (net (code "106") (name "VCC") (class "Default")
      (node (ref "J2") (pin "2") (pinfunction "2_2") (pintype "passive"))
      (node (ref "R26") (pin "2") (pinfunction "2_2") (pintype "passive"))
      (node (ref "SJ4") (pin "1") (pinfunction "1_1") (pintype "passive"))
    )
    (net (code "107") (name "unconnected-(J5-Pad1)") (class "Default")
      (node (ref "J5") (pin "1") (pinfunction "1_1") (pintype "passive"))
    )
    (net (code "108") (name "unconnected-(J5-Pad2)") (class "Default")
      (node (ref "J5") (pin "2") (pinfunction "2_2") (pintype "passive"))
    )
    (net (code "109") (name "unconnected-(J5-Pad3)") (class "Default")
      (node (ref "J5") (pin "3") (pinfunction "3_3") (pintype "passive"))
    )
    (net (code "110") (name "unconnected-(J5-Pad4)") (class "Default")
      (node (ref "J5") (pin "4") (pinfunction "4_4") (pintype "passive"))
    )
    (net (code "111") (name "unconnected-(J5-Pad5)") (class "Default")
      (node (ref "J5") (pin "5") (pinfunction "5_5") (pintype "passive"))
    )
    (net (code "112") (name "unconnected-(J5-Pad6)") (class "Default")
      (node (ref "J5") (pin "6") (pinfunction "6_6") (pintype "passive"))
    )
    (net (code "113") (name "unconnected-(J6-Pad1)") (class "Default")
      (node (ref "J6") (pin "1") (pinfunction "1_1") (pintype "passive"))
    )
    (net (code "114") (name "unconnected-(J6-Pad2)") (class "Default")
      (node (ref "J6") (pin "2") (pinfunction "2_2") (pintype "passive"))
    )
    (net (code "115") (name "unconnected-(J6-Pad3)") (class "Default")
      (node (ref "J6") (pin "3") (pinfunction "3_3") (pintype "passive"))
    )
    (net (code "116") (name "unconnected-(J6-Pad4)") (class "Default")
      (node (ref "J6") (pin "4") (pinfunction "4_4") (pintype "passive"))
    )
    (net (code "117") (name "unconnected-(J6-Pad5)") (class "Default")
      (node (ref "J6") (pin "5") (pinfunction "5_5") (pintype "passive"))
    )
    (net (code "118") (name "unconnected-(J6-Pad6)") (class "Default")
      (node (ref "J6") (pin "6") (pinfunction "6_6") (pintype "passive"))
    )
    (net (code "119") (name "unconnected-(J6-Pad7)") (class "Default")
      (node (ref "J6") (pin "7") (pinfunction "7_7") (pintype "passive"))
    )
    (net (code "120") (name "unconnected-(J6-Pad8)") (class "Default")
      (node (ref "J6") (pin "8") (pinfunction "8_8") (pintype "passive"))
    )
  )
)
